# Projekt.net
KiCad netlist of a schematic drawn in EAGLE
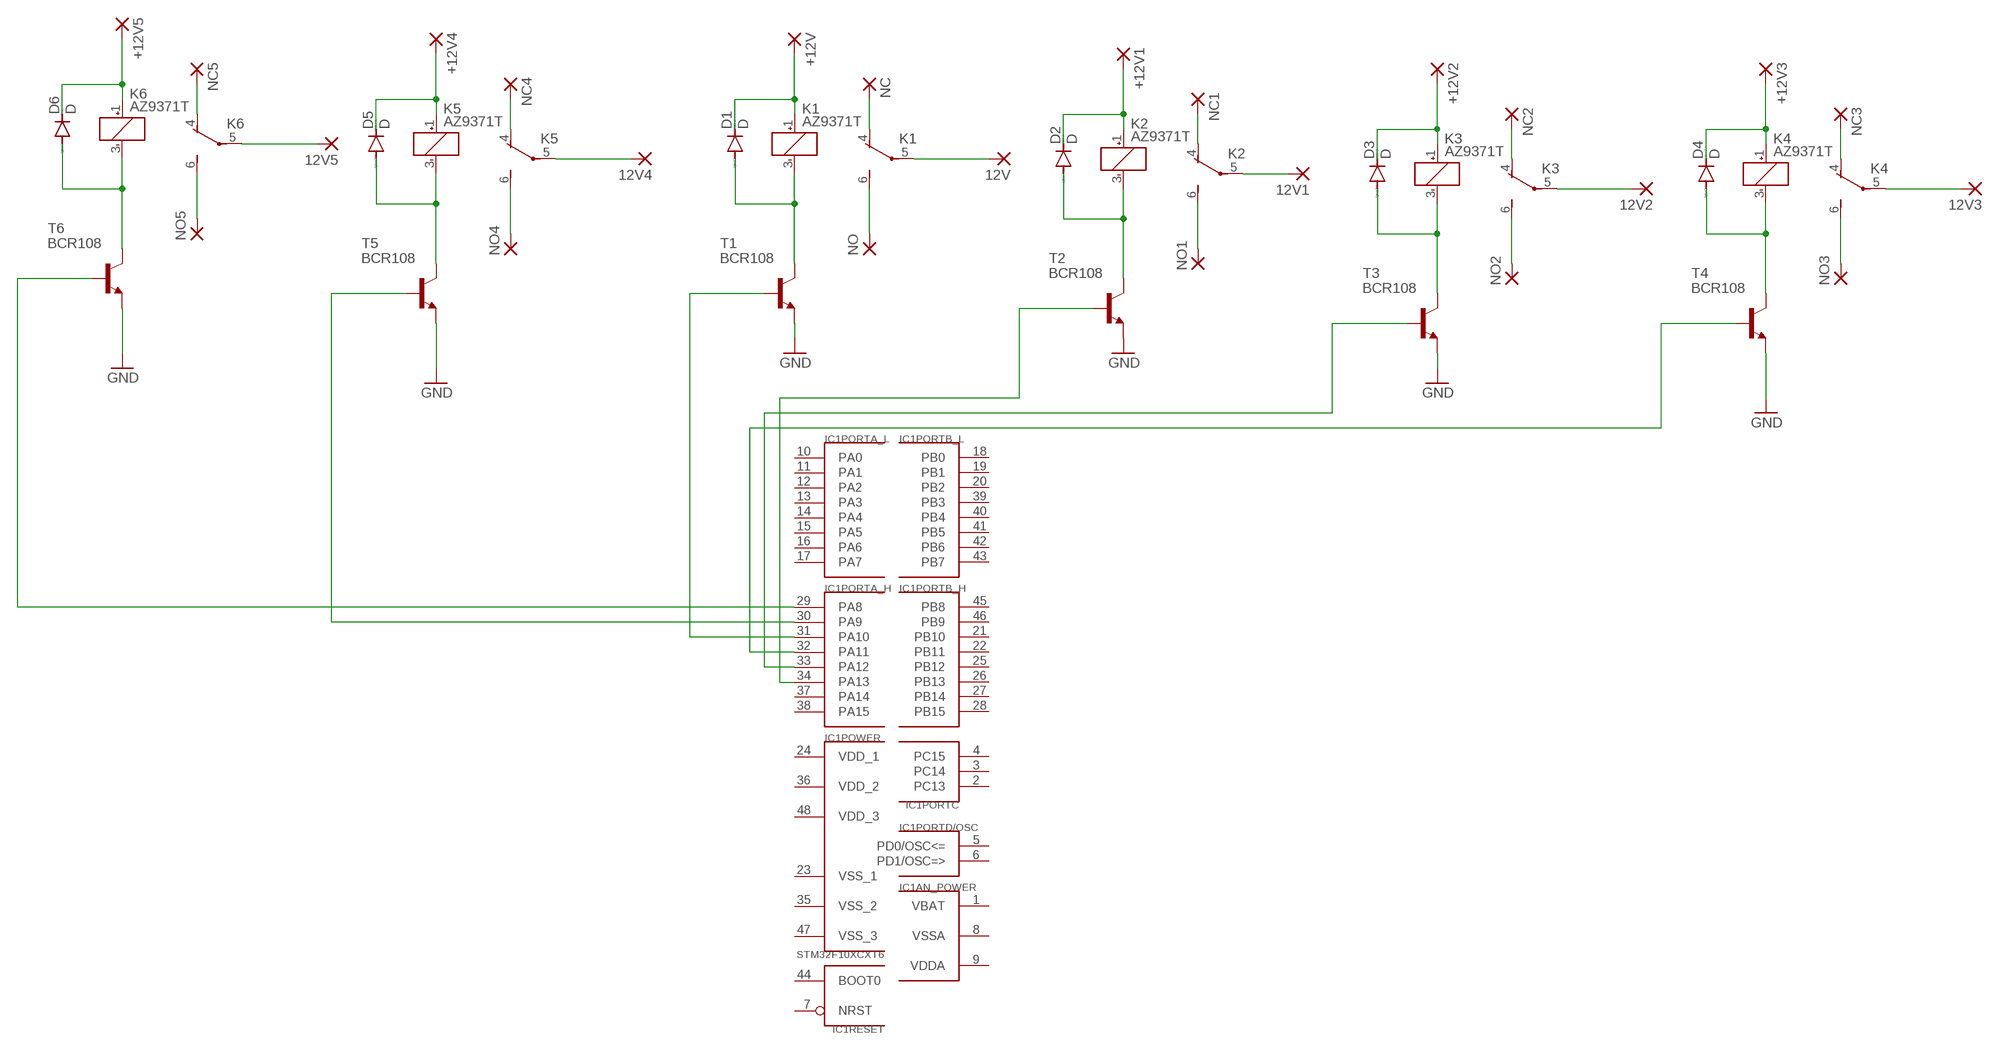
[diagram p0: schematic, sheet 1]

(export (version "E")
  (design (tool "Eeschema 10.0.6"))
  (components
    (comp (ref "+12V")
      (value "SMD2")
      (footprint "eagle-import:SMD1,27-2,54")
      (libsource (lib "eagle-import") (part "SMD2"))
    )
    (comp (ref "+12V1")
      (value "SMD2")
      (footprint "eagle-import:SMD1,27-2,54")
      (libsource (lib "eagle-import") (part "SMD2"))
    )
    (comp (ref "+12V2")
      (value "SMD2")
      (footprint "eagle-import:SMD1,27-2,54")
      (libsource (lib "eagle-import") (part "SMD2"))
    )
    (comp (ref "+12V3")
      (value "SMD2")
      (footprint "eagle-import:SMD1,27-2,54")
      (libsource (lib "eagle-import") (part "SMD2"))
    )
    (comp (ref "+12V4")
      (value "SMD2")
      (footprint "eagle-import:SMD1,27-2,54")
      (libsource (lib "eagle-import") (part "SMD2"))
    )
    (comp (ref "+12V5")
      (value "SMD2")
      (footprint "eagle-import:SMD1,27-2,54")
      (libsource (lib "eagle-import") (part "SMD2"))
    )
    (comp (ref "12V")
      (value "SMD2")
      (footprint "eagle-import:SMD1,27-2,54")
      (libsource (lib "eagle-import") (part "SMD2"))
    )
    (comp (ref "12V1")
      (value "SMD2")
      (footprint "eagle-import:SMD1,27-2,54")
      (libsource (lib "eagle-import") (part "SMD2"))
    )
    (comp (ref "12V2")
      (value "SMD2")
      (footprint "eagle-import:SMD1,27-2,54")
      (libsource (lib "eagle-import") (part "SMD2"))
    )
    (comp (ref "12V3")
      (value "SMD2")
      (footprint "eagle-import:SMD1,27-2,54")
      (libsource (lib "eagle-import") (part "SMD2"))
    )
    (comp (ref "12V4")
      (value "SMD2")
      (footprint "eagle-import:SMD1,27-2,54")
      (libsource (lib "eagle-import") (part "SMD2"))
    )
    (comp (ref "12V5")
      (value "SMD2")
      (footprint "eagle-import:SMD1,27-2,54")
      (libsource (lib "eagle-import") (part "SMD2"))
    )
    (comp (ref "D1")
      (value "D")
      (footprint "eagle-import:DO41-10")
      (libsource (lib "eagle-import") (part "1N4004"))
    )
    (comp (ref "D2")
      (value "D")
      (footprint "eagle-import:DO41-10")
      (libsource (lib "eagle-import") (part "1N4004"))
    )
    (comp (ref "D3")
      (value "D")
      (footprint "eagle-import:DO41-10")
      (libsource (lib "eagle-import") (part "1N4004"))
    )
    (comp (ref "D4")
      (value "D")
      (footprint "eagle-import:DO41-10")
      (libsource (lib "eagle-import") (part "1N4004"))
    )
    (comp (ref "D5")
      (value "D")
      (footprint "eagle-import:DO41-10")
      (libsource (lib "eagle-import") (part "1N4004"))
    )
    (comp (ref "D6")
      (value "D")
      (footprint "eagle-import:DO41-10")
      (libsource (lib "eagle-import") (part "1N4004"))
    )
    (comp (ref "IC1")
      (value "STM32F10XCXT6")
      (footprint "eagle-import:TQFP48")
      (libsource (lib "eagle-import") (part "STM32F10XCXT6"))
    )
    (comp (ref "K1")
      (value "AZ9371T")
      (footprint "eagle-import:TK")
      (fields (field (name "MF") "AROMAT/ MATSUSHITA") (field (name "MPN") "TK1-5V"))
      (libsource (lib "eagle-import") (part "TK1-?5V"))
    )
    (comp (ref "K2")
      (value "AZ9371T")
      (footprint "eagle-import:TK")
      (fields (field (name "MF") "AROMAT/ MATSUSHITA") (field (name "MPN") "TK1-5V"))
      (libsource (lib "eagle-import") (part "TK1-?5V"))
    )
    (comp (ref "K3")
      (value "AZ9371T")
      (footprint "eagle-import:TK")
      (fields (field (name "MF") "AROMAT/ MATSUSHITA") (field (name "MPN") "TK1-5V"))
      (libsource (lib "eagle-import") (part "TK1-?5V"))
    )
    (comp (ref "K4")
      (value "AZ9371T")
      (footprint "eagle-import:TK")
      (fields (field (name "MF") "AROMAT/ MATSUSHITA") (field (name "MPN") "TK1-5V"))
      (libsource (lib "eagle-import") (part "TK1-?5V"))
    )
    (comp (ref "K5")
      (value "AZ9371T")
      (footprint "eagle-import:TK")
      (fields (field (name "MF") "AROMAT/ MATSUSHITA") (field (name "MPN") "TK1-5V"))
      (libsource (lib "eagle-import") (part "TK1-?5V"))
    )
    (comp (ref "K6")
      (value "AZ9371T")
      (footprint "eagle-import:TK")
      (fields (field (name "MF") "AROMAT/ MATSUSHITA") (field (name "MPN") "TK1-5V"))
      (libsource (lib "eagle-import") (part "TK1-?5V"))
    )
    (comp (ref "NC")
      (value "SMD2")
      (footprint "eagle-import:SMD1,27-2,54")
      (libsource (lib "eagle-import") (part "SMD2"))
    )
    (comp (ref "NC1")
      (value "SMD2")
      (footprint "eagle-import:SMD1,27-2,54")
      (libsource (lib "eagle-import") (part "SMD2"))
    )
    (comp (ref "NC2")
      (value "SMD2")
      (footprint "eagle-import:SMD1,27-2,54")
      (libsource (lib "eagle-import") (part "SMD2"))
    )
    (comp (ref "NC3")
      (value "SMD2")
      (footprint "eagle-import:SMD1,27-2,54")
      (libsource (lib "eagle-import") (part "SMD2"))
    )
    (comp (ref "NC4")
      (value "SMD2")
      (footprint "eagle-import:SMD1,27-2,54")
      (libsource (lib "eagle-import") (part "SMD2"))
    )
    (comp (ref "NC5")
      (value "SMD2")
      (footprint "eagle-import:SMD1,27-2,54")
      (libsource (lib "eagle-import") (part "SMD2"))
    )
    (comp (ref "NO")
      (value "SMD2")
      (footprint "eagle-import:SMD1,27-2,54")
      (libsource (lib "eagle-import") (part "SMD2"))
    )
    (comp (ref "NO1")
      (value "SMD2")
      (footprint "eagle-import:SMD1,27-2,54")
      (libsource (lib "eagle-import") (part "SMD2"))
    )
    (comp (ref "NO2")
      (value "SMD2")
      (footprint "eagle-import:SMD1,27-2,54")
      (libsource (lib "eagle-import") (part "SMD2"))
    )
    (comp (ref "NO3")
      (value "SMD2")
      (footprint "eagle-import:SMD1,27-2,54")
      (libsource (lib "eagle-import") (part "SMD2"))
    )
    (comp (ref "NO4")
      (value "SMD2")
      (footprint "eagle-import:SMD1,27-2,54")
      (libsource (lib "eagle-import") (part "SMD2"))
    )
    (comp (ref "NO5")
      (value "SMD2")
      (footprint "eagle-import:SMD1,27-2,54")
      (libsource (lib "eagle-import") (part "SMD2"))
    )
    (comp (ref "T1")
      (value "BCR108")
      (footprint "eagle-import:TO5")
      (libsource (lib "eagle-import") (part "2N1613"))
    )
    (comp (ref "T2")
      (value "BCR108")
      (footprint "eagle-import:TO5")
      (libsource (lib "eagle-import") (part "2N1613"))
    )
    (comp (ref "T3")
      (value "BCR108")
      (footprint "eagle-import:TO5")
      (libsource (lib "eagle-import") (part "2N1613"))
    )
    (comp (ref "T4")
      (value "BCR108")
      (footprint "eagle-import:TO5")
      (libsource (lib "eagle-import") (part "2N1613"))
    )
    (comp (ref "T5")
      (value "BCR108")
      (footprint "eagle-import:TO5")
      (libsource (lib "eagle-import") (part "2N1613"))
    )
    (comp (ref "T6")
      (value "BCR108")
      (footprint "eagle-import:TO5")
      (libsource (lib "eagle-import") (part "2N1613"))
    )
  )
  (nets
    (net (code "1") (name "/VBAT") (class "Default")
      (node (ref "IC1") (pin "1") (pinfunction "VBAT_1") (pintype "power_in"))
    )
    (net (code "2") (name "/VDDA") (class "Default")
      (node (ref "IC1") (pin "9") (pinfunction "VDDA_9") (pintype "power_in"))
    )
    (net (code "3") (name "/VDD_1") (class "Default")
      (node (ref "IC1") (pin "24") (pinfunction "VDD_1_24") (pintype "power_in"))
    )
    (net (code "4") (name "/VDD_2") (class "Default")
      (node (ref "IC1") (pin "36") (pinfunction "VDD_2_36") (pintype "power_in"))
    )
    (net (code "5") (name "/VDD_3") (class "Default")
      (node (ref "IC1") (pin "48") (pinfunction "VDD_3_48") (pintype "power_in"))
    )
    (net (code "6") (name "/VSSA") (class "Default")
      (node (ref "IC1") (pin "8") (pinfunction "VSSA_8") (pintype "power_in"))
    )
    (net (code "7") (name "/VSS_1") (class "Default")
      (node (ref "IC1") (pin "23") (pinfunction "VSS_1_23") (pintype "power_in"))
    )
    (net (code "8") (name "/VSS_2") (class "Default")
      (node (ref "IC1") (pin "35") (pinfunction "VSS_2_35") (pintype "power_in"))
    )
    (net (code "9") (name "/VSS_3") (class "Default")
      (node (ref "IC1") (pin "47") (pinfunction "VSS_3_47") (pintype "power_in"))
    )
    (net (code "10") (name "GND") (class "Default")
      (node (ref "T1") (pin "1") (pinfunction "E_1") (pintype "passive"))
      (node (ref "T2") (pin "1") (pinfunction "E_1") (pintype "passive"))
      (node (ref "T3") (pin "1") (pinfunction "E_1") (pintype "passive"))
      (node (ref "T4") (pin "1") (pinfunction "E_1") (pintype "passive"))
      (node (ref "T5") (pin "1") (pinfunction "E_1") (pintype "passive"))
      (node (ref "T6") (pin "1") (pinfunction "E_1") (pintype "passive"))
    )
    (net (code "11") (name "Net-(+12V-P)") (class "Default")
      (node (ref "+12V") (pin "1") (pinfunction "P_1") (pintype "passive"))
      (node (ref "D1") (pin "C") (pinfunction "C_C") (pintype "passive"))
      (node (ref "K1") (pin "1") (pinfunction "+_1") (pintype "passive"))
    )
    (net (code "12") (name "Net-(+12V1-P)") (class "Default")
      (node (ref "+12V1") (pin "1") (pinfunction "P_1") (pintype "passive"))
      (node (ref "D2") (pin "C") (pinfunction "C_C") (pintype "passive"))
      (node (ref "K2") (pin "1") (pinfunction "+_1") (pintype "passive"))
    )
    (net (code "13") (name "Net-(+12V2-P)") (class "Default")
      (node (ref "+12V2") (pin "1") (pinfunction "P_1") (pintype "passive"))
      (node (ref "D3") (pin "C") (pinfunction "C_C") (pintype "passive"))
      (node (ref "K3") (pin "1") (pinfunction "+_1") (pintype "passive"))
    )
    (net (code "14") (name "Net-(+12V3-P)") (class "Default")
      (node (ref "+12V3") (pin "1") (pinfunction "P_1") (pintype "passive"))
      (node (ref "D4") (pin "C") (pinfunction "C_C") (pintype "passive"))
      (node (ref "K4") (pin "1") (pinfunction "+_1") (pintype "passive"))
    )
    (net (code "15") (name "Net-(+12V4-P)") (class "Default")
      (node (ref "+12V4") (pin "1") (pinfunction "P_1") (pintype "passive"))
      (node (ref "D5") (pin "C") (pinfunction "C_C") (pintype "passive"))
      (node (ref "K5") (pin "1") (pinfunction "+_1") (pintype "passive"))
    )
    (net (code "16") (name "Net-(+12V5-P)") (class "Default")
      (node (ref "+12V5") (pin "1") (pinfunction "P_1") (pintype "passive"))
      (node (ref "D6") (pin "C") (pinfunction "C_C") (pintype "passive"))
      (node (ref "K6") (pin "1") (pinfunction "+_1") (pintype "passive"))
    )
    (net (code "17") (name "Net-(12V-P)") (class "Default")
      (node (ref "12V") (pin "1") (pinfunction "P_1") (pintype "passive"))
      (node (ref "K1") (pin "5") (pinfunction "P_5") (pintype "passive"))
    )
    (net (code "18") (name "Net-(12V1-P)") (class "Default")
      (node (ref "12V1") (pin "1") (pinfunction "P_1") (pintype "passive"))
      (node (ref "K2") (pin "5") (pinfunction "P_5") (pintype "passive"))
    )
    (net (code "19") (name "Net-(12V2-P)") (class "Default")
      (node (ref "12V2") (pin "1") (pinfunction "P_1") (pintype "passive"))
      (node (ref "K3") (pin "5") (pinfunction "P_5") (pintype "passive"))
    )
    (net (code "20") (name "Net-(12V3-P)") (class "Default")
      (node (ref "12V3") (pin "1") (pinfunction "P_1") (pintype "passive"))
      (node (ref "K4") (pin "5") (pinfunction "P_5") (pintype "passive"))
    )
    (net (code "21") (name "Net-(12V4-P)") (class "Default")
      (node (ref "12V4") (pin "1") (pinfunction "P_1") (pintype "passive"))
      (node (ref "K5") (pin "5") (pinfunction "P_5") (pintype "passive"))
    )
    (net (code "22") (name "Net-(12V5-P)") (class "Default")
      (node (ref "12V5") (pin "1") (pinfunction "P_1") (pintype "passive"))
      (node (ref "K6") (pin "5") (pinfunction "P_5") (pintype "passive"))
    )
    (net (code "23") (name "Net-(IC1B-PA8)") (class "Default")
      (node (ref "IC1") (pin "29") (pinfunction "PA8_29") (pintype "bidirectional"))
      (node (ref "T6") (pin "2") (pinfunction "B_2") (pintype "passive"))
    )
    (net (code "24") (name "Net-(IC1B-PA9)") (class "Default")
      (node (ref "IC1") (pin "30") (pinfunction "PA9_30") (pintype "bidirectional"))
      (node (ref "T5") (pin "2") (pinfunction "B_2") (pintype "passive"))
    )
    (net (code "25") (name "Net-(IC1B-PA10)") (class "Default")
      (node (ref "IC1") (pin "31") (pinfunction "PA10_31") (pintype "bidirectional"))
      (node (ref "T1") (pin "2") (pinfunction "B_2") (pintype "passive"))
    )
    (net (code "26") (name "Net-(IC1B-PA11)") (class "Default")
      (node (ref "IC1") (pin "32") (pinfunction "PA11_32") (pintype "bidirectional"))
      (node (ref "T4") (pin "2") (pinfunction "B_2") (pintype "passive"))
    )
    (net (code "27") (name "Net-(IC1B-PA12)") (class "Default")
      (node (ref "IC1") (pin "33") (pinfunction "PA12_33") (pintype "bidirectional"))
      (node (ref "T3") (pin "2") (pinfunction "B_2") (pintype "passive"))
    )
    (net (code "28") (name "Net-(IC1B-PA13)") (class "Default")
      (node (ref "IC1") (pin "34") (pinfunction "PA13_34") (pintype "bidirectional"))
      (node (ref "T2") (pin "2") (pinfunction "B_2") (pintype "passive"))
    )
    (net (code "29") (name "Net-(K1A--)") (class "Default")
      (node (ref "D1") (pin "A") (pinfunction "A_A") (pintype "passive"))
      (node (ref "K1") (pin "3") (pinfunction "-_3") (pintype "passive"))
      (node (ref "T1") (pin "3") (pinfunction "C_3") (pintype "passive"))
    )
    (net (code "30") (name "Net-(K1B-O)") (class "Default")
      (node (ref "K1") (pin "4") (pinfunction "O_4") (pintype "passive"))
      (node (ref "NC") (pin "1") (pinfunction "P_1") (pintype "passive"))
    )
    (net (code "31") (name "Net-(K1B-S)") (class "Default")
      (node (ref "K1") (pin "6") (pinfunction "S_6") (pintype "passive"))
      (node (ref "NO") (pin "1") (pinfunction "P_1") (pintype "passive"))
    )
    (net (code "32") (name "Net-(K2A--)") (class "Default")
      (node (ref "D2") (pin "A") (pinfunction "A_A") (pintype "passive"))
      (node (ref "K2") (pin "3") (pinfunction "-_3") (pintype "passive"))
      (node (ref "T2") (pin "3") (pinfunction "C_3") (pintype "passive"))
    )
    (net (code "33") (name "Net-(K2B-O)") (class "Default")
      (node (ref "K2") (pin "4") (pinfunction "O_4") (pintype "passive"))
      (node (ref "NC1") (pin "1") (pinfunction "P_1") (pintype "passive"))
    )
    (net (code "34") (name "Net-(K2B-S)") (class "Default")
      (node (ref "K2") (pin "6") (pinfunction "S_6") (pintype "passive"))
      (node (ref "NO1") (pin "1") (pinfunction "P_1") (pintype "passive"))
    )
    (net (code "35") (name "Net-(K3A--)") (class "Default")
      (node (ref "D3") (pin "A") (pinfunction "A_A") (pintype "passive"))
      (node (ref "K3") (pin "3") (pinfunction "-_3") (pintype "passive"))
      (node (ref "T3") (pin "3") (pinfunction "C_3") (pintype "passive"))
    )
    (net (code "36") (name "Net-(K3B-O)") (class "Default")
      (node (ref "K3") (pin "4") (pinfunction "O_4") (pintype "passive"))
      (node (ref "NC2") (pin "1") (pinfunction "P_1") (pintype "passive"))
    )
    (net (code "37") (name "Net-(K3B-S)") (class "Default")
      (node (ref "K3") (pin "6") (pinfunction "S_6") (pintype "passive"))
      (node (ref "NO2") (pin "1") (pinfunction "P_1") (pintype "passive"))
    )
    (net (code "38") (name "Net-(K4A--)") (class "Default")
      (node (ref "D4") (pin "A") (pinfunction "A_A") (pintype "passive"))
      (node (ref "K4") (pin "3") (pinfunction "-_3") (pintype "passive"))
      (node (ref "T4") (pin "3") (pinfunction "C_3") (pintype "passive"))
    )
    (net (code "39") (name "Net-(K4B-O)") (class "Default")
      (node (ref "K4") (pin "4") (pinfunction "O_4") (pintype "passive"))
      (node (ref "NC3") (pin "1") (pinfunction "P_1") (pintype "passive"))
    )
    (net (code "40") (name "Net-(K4B-S)") (class "Default")
      (node (ref "K4") (pin "6") (pinfunction "S_6") (pintype "passive"))
      (node (ref "NO3") (pin "1") (pinfunction "P_1") (pintype "passive"))
    )
    (net (code "41") (name "Net-(K5A--)") (class "Default")
      (node (ref "D5") (pin "A") (pinfunction "A_A") (pintype "passive"))
      (node (ref "K5") (pin "3") (pinfunction "-_3") (pintype "passive"))
      (node (ref "T5") (pin "3") (pinfunction "C_3") (pintype "passive"))
    )
    (net (code "42") (name "Net-(K5B-O)") (class "Default")
      (node (ref "K5") (pin "4") (pinfunction "O_4") (pintype "passive"))
      (node (ref "NC4") (pin "1") (pinfunction "P_1") (pintype "passive"))
    )
    (net (code "43") (name "Net-(K5B-S)") (class "Default")
      (node (ref "K5") (pin "6") (pinfunction "S_6") (pintype "passive"))
      (node (ref "NO4") (pin "1") (pinfunction "P_1") (pintype "passive"))
    )
    (net (code "44") (name "Net-(K6A--)") (class "Default")
      (node (ref "D6") (pin "A") (pinfunction "A_A") (pintype "passive"))
      (node (ref "K6") (pin "3") (pinfunction "-_3") (pintype "passive"))
      (node (ref "T6") (pin "3") (pinfunction "C_3") (pintype "passive"))
    )
    (net (code "45") (name "Net-(K6B-O)") (class "Default")
      (node (ref "K6") (pin "4") (pinfunction "O_4") (pintype "passive"))
      (node (ref "NC5") (pin "1") (pinfunction "P_1") (pintype "passive"))
    )
    (net (code "46") (name "Net-(K6B-S)") (class "Default")
      (node (ref "K6") (pin "6") (pinfunction "S_6") (pintype "passive"))
      (node (ref "NO5") (pin "1") (pinfunction "P_1") (pintype "passive"))
    )
    (net (code "47") (name "unconnected-(IC1B-PA14-Pad37)") (class "Default")
      (node (ref "IC1") (pin "37") (pinfunction "PA14_37") (pintype "bidirectional"))
    )
    (net (code "48") (name "unconnected-(IC1B-PA15-Pad38)") (class "Default")
      (node (ref "IC1") (pin "38") (pinfunction "PA15_38") (pintype "bidirectional"))
    )
    (net (code "49") (name "unconnected-(IC1C-PA0-Pad10)") (class "Default")
      (node (ref "IC1") (pin "10") (pinfunction "PA0_10") (pintype "bidirectional"))
    )
    (net (code "50") (name "unconnected-(IC1C-PA1-Pad11)") (class "Default")
      (node (ref "IC1") (pin "11") (pinfunction "PA1_11") (pintype "bidirectional"))
    )
    (net (code "51") (name "unconnected-(IC1C-PA2-Pad12)") (class "Default")
      (node (ref "IC1") (pin "12") (pinfunction "PA2_12") (pintype "bidirectional"))
    )
    (net (code "52") (name "unconnected-(IC1C-PA3-Pad13)") (class "Default")
      (node (ref "IC1") (pin "13") (pinfunction "PA3_13") (pintype "bidirectional"))
    )
    (net (code "53") (name "unconnected-(IC1C-PA4-Pad14)") (class "Default")
      (node (ref "IC1") (pin "14") (pinfunction "PA4_14") (pintype "bidirectional"))
    )
    (net (code "54") (name "unconnected-(IC1C-PA5-Pad15)") (class "Default")
      (node (ref "IC1") (pin "15") (pinfunction "PA5_15") (pintype "bidirectional"))
    )
    (net (code "55") (name "unconnected-(IC1C-PA6-Pad16)") (class "Default")
      (node (ref "IC1") (pin "16") (pinfunction "PA6_16") (pintype "bidirectional"))
    )
    (net (code "56") (name "unconnected-(IC1C-PA7-Pad17)") (class "Default")
      (node (ref "IC1") (pin "17") (pinfunction "PA7_17") (pintype "bidirectional"))
    )
    (net (code "57") (name "unconnected-(IC1D-PB8-Pad45)") (class "Default")
      (node (ref "IC1") (pin "45") (pinfunction "PB8_45") (pintype "bidirectional"))
    )
    (net (code "58") (name "unconnected-(IC1D-PB9-Pad46)") (class "Default")
      (node (ref "IC1") (pin "46") (pinfunction "PB9_46") (pintype "bidirectional"))
    )
    (net (code "59") (name "unconnected-(IC1D-PB10-Pad21)") (class "Default")
      (node (ref "IC1") (pin "21") (pinfunction "PB10_21") (pintype "bidirectional"))
    )
    (net (code "60") (name "unconnected-(IC1D-PB11-Pad22)") (class "Default")
      (node (ref "IC1") (pin "22") (pinfunction "PB11_22") (pintype "bidirectional"))
    )
    (net (code "61") (name "unconnected-(IC1D-PB12-Pad25)") (class "Default")
      (node (ref "IC1") (pin "25") (pinfunction "PB12_25") (pintype "bidirectional"))
    )
    (net (code "62") (name "unconnected-(IC1D-PB13-Pad26)") (class "Default")
      (node (ref "IC1") (pin "26") (pinfunction "PB13_26") (pintype "bidirectional"))
    )
    (net (code "63") (name "unconnected-(IC1D-PB14-Pad27)") (class "Default")
      (node (ref "IC1") (pin "27") (pinfunction "PB14_27") (pintype "bidirectional"))
    )
    (net (code "64") (name "unconnected-(IC1D-PB15-Pad28)") (class "Default")
      (node (ref "IC1") (pin "28") (pinfunction "PB15_28") (pintype "bidirectional"))
    )
    (net (code "65") (name "unconnected-(IC1E-PB0-Pad18)") (class "Default")
      (node (ref "IC1") (pin "18") (pinfunction "PB0_18") (pintype "bidirectional"))
    )
    (net (code "66") (name "unconnected-(IC1E-PB1-Pad19)") (class "Default")
      (node (ref "IC1") (pin "19") (pinfunction "PB1_19") (pintype "bidirectional"))
    )
    (net (code "67") (name "unconnected-(IC1E-PB2-Pad20)") (class "Default")
      (node (ref "IC1") (pin "20") (pinfunction "PB2_20") (pintype "bidirectional"))
    )
    (net (code "68") (name "unconnected-(IC1E-PB3-Pad39)") (class "Default")
      (node (ref "IC1") (pin "39") (pinfunction "PB3_39") (pintype "bidirectional"))
    )
    (net (code "69") (name "unconnected-(IC1E-PB4-Pad40)") (class "Default")
      (node (ref "IC1") (pin "40") (pinfunction "PB4_40") (pintype "bidirectional"))
    )
    (net (code "70") (name "unconnected-(IC1E-PB5-Pad41)") (class "Default")
      (node (ref "IC1") (pin "41") (pinfunction "PB5_41") (pintype "bidirectional"))
    )
    (net (code "71") (name "unconnected-(IC1E-PB6-Pad42)") (class "Default")
      (node (ref "IC1") (pin "42") (pinfunction "PB6_42") (pintype "bidirectional"))
    )
    (net (code "72") (name "unconnected-(IC1E-PB7-Pad43)") (class "Default")
      (node (ref "IC1") (pin "43") (pinfunction "PB7_43") (pintype "bidirectional"))
    )
    (net (code "73") (name "unconnected-(IC1F-PC13-Pad2)") (class "Default")
      (node (ref "IC1") (pin "2") (pinfunction "PC13_2") (pintype "bidirectional"))
    )
    (net (code "74") (name "unconnected-(IC1F-PC14-Pad3)") (class "Default")
      (node (ref "IC1") (pin "3") (pinfunction "PC14_3") (pintype "bidirectional"))
    )
    (net (code "75") (name "unconnected-(IC1F-PC15-Pad4)") (class "Default")
      (node (ref "IC1") (pin "4") (pinfunction "PC15_4") (pintype "bidirectional"))
    )
    (net (code "76") (name "unconnected-(IC1G-PD0{slash}OSC<=-Pad5)") (class "Default")
      (node (ref "IC1") (pin "5") (pinfunction "PD0/OSC<=_5") (pintype "bidirectional"))
    )
    (net (code "77") (name "unconnected-(IC1G-PD1{slash}OSC=>-Pad6)") (class "Default")
      (node (ref "IC1") (pin "6") (pinfunction "PD1/OSC=>_6") (pintype "bidirectional"))
    )
    (net (code "78") (name "unconnected-(IC1I-BOOT0-Pad44)") (class "Default")
      (node (ref "IC1") (pin "44") (pinfunction "BOOT0_44") (pintype "input"))
    )
    (net (code "79") (name "unconnected-(IC1I-NRST-Pad7)") (class "Default")
      (node (ref "IC1") (pin "7") (pinfunction "NRST_7") (pintype "input"))
    )
  )
)
